# implant7.net
KiCad netlist of a schematic drawn in EAGLE
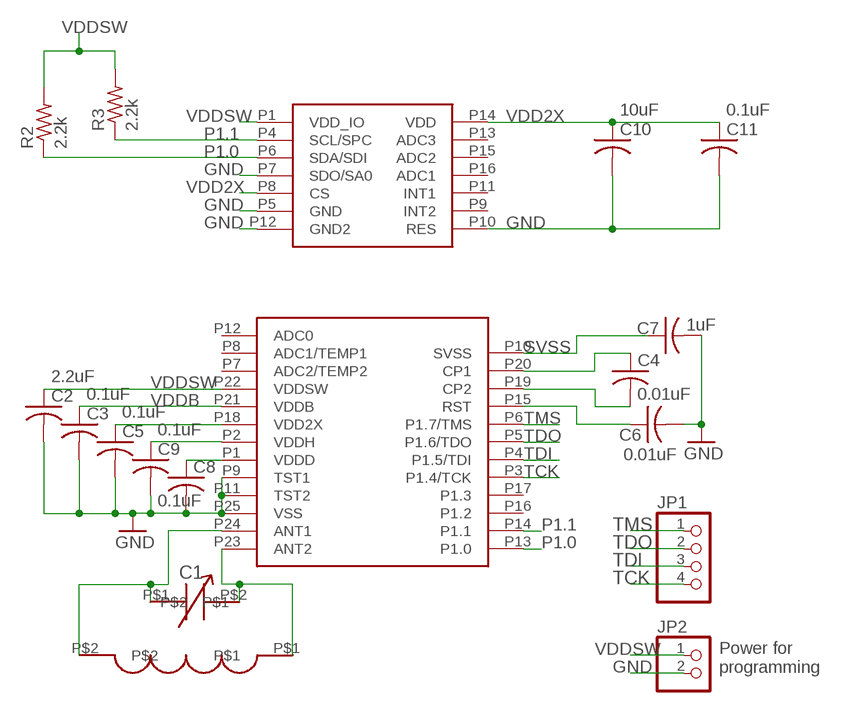
[diagram p0: schematic, sheet 1]

(export (version "E")
  (design (tool "Eeschema 10.0.6"))
  (components
    (comp (ref "C2")
      (value "2.2uF")
      (footprint "eagle-import:C0805")
      (libsource (lib "eagle-import") (part "C-USC0805"))
    )
    (comp (ref "C3")
      (value "0.1uF")
      (footprint "eagle-import:C0805")
      (libsource (lib "eagle-import") (part "C-USC0805"))
    )
    (comp (ref "C4")
      (value "0.01uF")
      (footprint "eagle-import:C0805")
      (libsource (lib "eagle-import") (part "C-USC0805"))
    )
    (comp (ref "C5")
      (value "0.1uF")
      (footprint "eagle-import:C0805")
      (libsource (lib "eagle-import") (part "C-USC0805"))
    )
    (comp (ref "C6")
      (value "0.01uF")
      (footprint "eagle-import:C0805")
      (libsource (lib "eagle-import") (part "C-USC0805"))
    )
    (comp (ref "C7")
      (value "1uF")
      (footprint "eagle-import:C0805")
      (libsource (lib "eagle-import") (part "C-USC0805"))
    )
    (comp (ref "C8")
      (value "0.1uF")
      (footprint "eagle-import:C0805")
      (libsource (lib "eagle-import") (part "C-USC0805"))
    )
    (comp (ref "C9")
      (value "0.1uF")
      (footprint "eagle-import:C0805")
      (libsource (lib "eagle-import") (part "C-USC0805"))
    )
    (comp (ref "C10")
      (value "10uF")
      (footprint "eagle-import:C0805")
      (libsource (lib "eagle-import") (part "C-USC0805"))
    )
    (comp (ref "C11")
      (value "0.1uF")
      (footprint "eagle-import:C0805")
      (libsource (lib "eagle-import") (part "C-USC0805"))
    )
    (comp (ref "JP1")
      (value "PINHD-1X4")
      (footprint "eagle-import:1X04")
      (libsource (lib "eagle-import") (part "PINHD-1X4"))
    )
    (comp (ref "JP2")
      (value "PINHD-1X2")
      (footprint "eagle-import:1X02")
      (libsource (lib "eagle-import") (part "PINHD-1X2"))
    )
    (comp (ref "R2")
      (value "2.2k")
      (footprint "eagle-import:R0805")
      (libsource (lib "eagle-import") (part "R-US_R0805"))
    )
    (comp (ref "R3")
      (value "2.2k")
      (footprint "eagle-import:R0805")
      (libsource (lib "eagle-import") (part "R-US_R0805"))
    )
    (comp (ref "U$1")
      (value "RF430FRL152H")
      (footprint "eagle-import:VQFN")
      (libsource (lib "eagle-import") (part "RF430FRL152H"))
    )
    (comp (ref "U$2")
      (value "COILCOIL3")
      (footprint "eagle-import:COIL3")
      (libsource (lib "eagle-import") (part "COILCOIL3"))
    )
    (comp (ref "U$3")
      (value "VAR_CAP")
      (footprint "eagle-import:VAR_CAP")
      (libsource (lib "eagle-import") (part "VAR_CAP"))
    )
    (comp (ref "U$4")
      (value "LIS3DH")
      (footprint "eagle-import:LGA-16")
      (libsource (lib "eagle-import") (part "LIS3DH"))
    )
  )
  (nets
    (net (code "1") (name "/P1.0") (class "Default")
      (node (ref "R2") (pin "1") (pinfunction "1_1") (pintype "passive"))
      (node (ref "U$1") (pin "P13") (pinfunction "P1.0_P13") (pintype "bidirectional"))
      (node (ref "U$4") (pin "P6") (pinfunction "SDA/SDI_P6") (pintype "bidirectional"))
    )
    (net (code "2") (name "/P1.1") (class "Default")
      (node (ref "R3") (pin "1") (pinfunction "1_1") (pintype "passive"))
      (node (ref "U$1") (pin "P14") (pinfunction "P1.1_P14") (pintype "bidirectional"))
      (node (ref "U$4") (pin "P4") (pinfunction "SCL/SPC_P4") (pintype "bidirectional"))
    )
    (net (code "3") (name "/SVSS") (class "Default")
      (node (ref "C7") (pin "1") (pinfunction "1_1") (pintype "passive"))
      (node (ref "U$1") (pin "P10") (pinfunction "SVSS_P10") (pintype "bidirectional"))
    )
    (net (code "4") (name "/TCK") (class "Default")
      (node (ref "JP1") (pin "4") (pinfunction "4_4") (pintype "passive"))
      (node (ref "U$1") (pin "P3") (pinfunction "P1.4/TCK_P3") (pintype "bidirectional"))
    )
    (net (code "5") (name "/TDI") (class "Default")
      (node (ref "JP1") (pin "3") (pinfunction "3_3") (pintype "passive"))
      (node (ref "U$1") (pin "P4") (pinfunction "P1.5/TDI_P4") (pintype "bidirectional"))
    )
    (net (code "6") (name "/TDO") (class "Default")
      (node (ref "JP1") (pin "2") (pinfunction "2_2") (pintype "passive"))
      (node (ref "U$1") (pin "P5") (pinfunction "P1.6/TDO_P5") (pintype "bidirectional"))
    )
    (net (code "7") (name "/TMS") (class "Default")
      (node (ref "JP1") (pin "1") (pinfunction "1_1") (pintype "passive"))
      (node (ref "U$1") (pin "P6") (pinfunction "P1.7/TMS_P6") (pintype "bidirectional"))
    )
    (net (code "8") (name "/VDD2X") (class "Default")
      (node (ref "C10") (pin "1") (pinfunction "1_1") (pintype "passive"))
      (node (ref "C11") (pin "1") (pinfunction "1_1") (pintype "passive"))
      (node (ref "C5") (pin "1") (pinfunction "1_1") (pintype "passive"))
      (node (ref "U$1") (pin "P18") (pinfunction "VDD2X_P18") (pintype "bidirectional"))
      (node (ref "U$4") (pin "P14") (pinfunction "VDD_P14") (pintype "bidirectional"))
      (node (ref "U$4") (pin "P8") (pinfunction "CS_P8") (pintype "bidirectional"))
    )
    (net (code "9") (name "/VDDB") (class "Default")
      (node (ref "C3") (pin "1") (pinfunction "1_1") (pintype "passive"))
      (node (ref "U$1") (pin "P21") (pinfunction "VDDB_P21") (pintype "bidirectional"))
    )
    (net (code "10") (name "/VDDSW") (class "Default")
      (node (ref "C2") (pin "1") (pinfunction "1_1") (pintype "passive"))
      (node (ref "JP2") (pin "1") (pinfunction "1_1") (pintype "passive"))
      (node (ref "R2") (pin "2") (pinfunction "2_2") (pintype "passive"))
      (node (ref "R3") (pin "2") (pinfunction "2_2") (pintype "passive"))
      (node (ref "U$1") (pin "P22") (pinfunction "VDDSW_P22") (pintype "bidirectional"))
      (node (ref "U$4") (pin "P1") (pinfunction "VDD_IO_P1") (pintype "bidirectional"))
    )
    (net (code "11") (name "GND") (class "Default")
      (node (ref "C10") (pin "2") (pinfunction "2_2") (pintype "passive"))
      (node (ref "C11") (pin "2") (pinfunction "2_2") (pintype "passive"))
      (node (ref "C2") (pin "2") (pinfunction "2_2") (pintype "passive"))
      (node (ref "C3") (pin "2") (pinfunction "2_2") (pintype "passive"))
      (node (ref "C5") (pin "2") (pinfunction "2_2") (pintype "passive"))
      (node (ref "C6") (pin "2") (pinfunction "2_2") (pintype "passive"))
      (node (ref "C7") (pin "2") (pinfunction "2_2") (pintype "passive"))
      (node (ref "C8") (pin "2") (pinfunction "2_2") (pintype "passive"))
      (node (ref "C9") (pin "2") (pinfunction "2_2") (pintype "passive"))
      (node (ref "JP2") (pin "2") (pinfunction "2_2") (pintype "passive"))
      (node (ref "U$1") (pin "P11") (pinfunction "TST2_P11") (pintype "bidirectional"))
      (node (ref "U$1") (pin "P25") (pinfunction "VSS_P25") (pintype "bidirectional"))
      (node (ref "U$1") (pin "P9") (pinfunction "TST1_P9") (pintype "bidirectional"))
      (node (ref "U$4") (pin "P10") (pinfunction "RES_P10") (pintype "bidirectional"))
      (node (ref "U$4") (pin "P12") (pinfunction "GND2_P12") (pintype "bidirectional"))
      (node (ref "U$4") (pin "P5") (pinfunction "GND_P5") (pintype "bidirectional"))
      (node (ref "U$4") (pin "P7") (pinfunction "SDO/SA0_P7") (pintype "bidirectional"))
    )
    (net (code "12") (name "Net-(U$1-ANT1)") (class "Default")
      (node (ref "U$1") (pin "P24") (pinfunction "ANT1_P24") (pintype "bidirectional"))
      (node (ref "U$2") (pin "P$2") (pinfunction "P$2_P$2") (pintype "bidirectional"))
      (node (ref "U$3") (pin "P$1") (pinfunction "P$1_P$1") (pintype "bidirectional"))
    )
    (net (code "13") (name "Net-(U$1-ANT2)") (class "Default")
      (node (ref "U$1") (pin "P23") (pinfunction "ANT2_P23") (pintype "bidirectional"))
      (node (ref "U$2") (pin "P$1") (pinfunction "P$1_P$1") (pintype "bidirectional"))
      (node (ref "U$3") (pin "P$2") (pinfunction "P$2_P$2") (pintype "bidirectional"))
    )
    (net (code "14") (name "Net-(U$1-CP1)") (class "Default")
      (node (ref "C4") (pin "1") (pinfunction "1_1") (pintype "passive"))
      (node (ref "U$1") (pin "P20") (pinfunction "CP1_P20") (pintype "bidirectional"))
    )
    (net (code "15") (name "Net-(U$1-CP2)") (class "Default")
      (node (ref "C4") (pin "2") (pinfunction "2_2") (pintype "passive"))
      (node (ref "U$1") (pin "P19") (pinfunction "CP2_P19") (pintype "bidirectional"))
    )
    (net (code "16") (name "Net-(U$1-RST)") (class "Default")
      (node (ref "C6") (pin "1") (pinfunction "1_1") (pintype "passive"))
      (node (ref "U$1") (pin "P15") (pinfunction "RST_P15") (pintype "bidirectional"))
    )
    (net (code "17") (name "Net-(U$1-VDDD)") (class "Default")
      (node (ref "C8") (pin "1") (pinfunction "1_1") (pintype "passive"))
      (node (ref "U$1") (pin "P1") (pinfunction "VDDD_P1") (pintype "bidirectional"))
    )
    (net (code "18") (name "Net-(U$1-VDDH)") (class "Default")
      (node (ref "C9") (pin "1") (pinfunction "1_1") (pintype "passive"))
      (node (ref "U$1") (pin "P2") (pinfunction "VDDH_P2") (pintype "bidirectional"))
    )
    (net (code "19") (name "unconnected-(U$1-ADC0-PadP12)") (class "Default")
      (node (ref "U$1") (pin "P12") (pinfunction "ADC0_P12") (pintype "bidirectional"))
    )
    (net (code "20") (name "unconnected-(U$1-ADC1{slash}TEMP1-PadP8)") (class "Default")
      (node (ref "U$1") (pin "P8") (pinfunction "ADC1/TEMP1_P8") (pintype "bidirectional"))
    )
    (net (code "21") (name "unconnected-(U$1-ADC2{slash}TEMP2-PadP7)") (class "Default")
      (node (ref "U$1") (pin "P7") (pinfunction "ADC2/TEMP2_P7") (pintype "bidirectional"))
    )
    (net (code "22") (name "unconnected-(U$1-P1.2-PadP16)") (class "Default")
      (node (ref "U$1") (pin "P16") (pinfunction "P1.2_P16") (pintype "bidirectional"))
    )
    (net (code "23") (name "unconnected-(U$1-P1.3-PadP17)") (class "Default")
      (node (ref "U$1") (pin "P17") (pinfunction "P1.3_P17") (pintype "bidirectional"))
    )
    (net (code "24") (name "unconnected-(U$4-ADC1-PadP16)") (class "Default")
      (node (ref "U$4") (pin "P16") (pinfunction "ADC1_P16") (pintype "bidirectional"))
    )
    (net (code "25") (name "unconnected-(U$4-ADC2-PadP15)") (class "Default")
      (node (ref "U$4") (pin "P15") (pinfunction "ADC2_P15") (pintype "bidirectional"))
    )
    (net (code "26") (name "unconnected-(U$4-ADC3-PadP13)") (class "Default")
      (node (ref "U$4") (pin "P13") (pinfunction "ADC3_P13") (pintype "bidirectional"))
    )
    (net (code "27") (name "unconnected-(U$4-INT1-PadP11)") (class "Default")
      (node (ref "U$4") (pin "P11") (pinfunction "INT1_P11") (pintype "bidirectional"))
    )
    (net (code "28") (name "unconnected-(U$4-INT2-PadP9)") (class "Default")
      (node (ref "U$4") (pin "P9") (pinfunction "INT2_P9") (pintype "bidirectional"))
    )
  )
)
